# WT8266_universal_v01.net
KiCad netlist of a schematic drawn in EAGLE
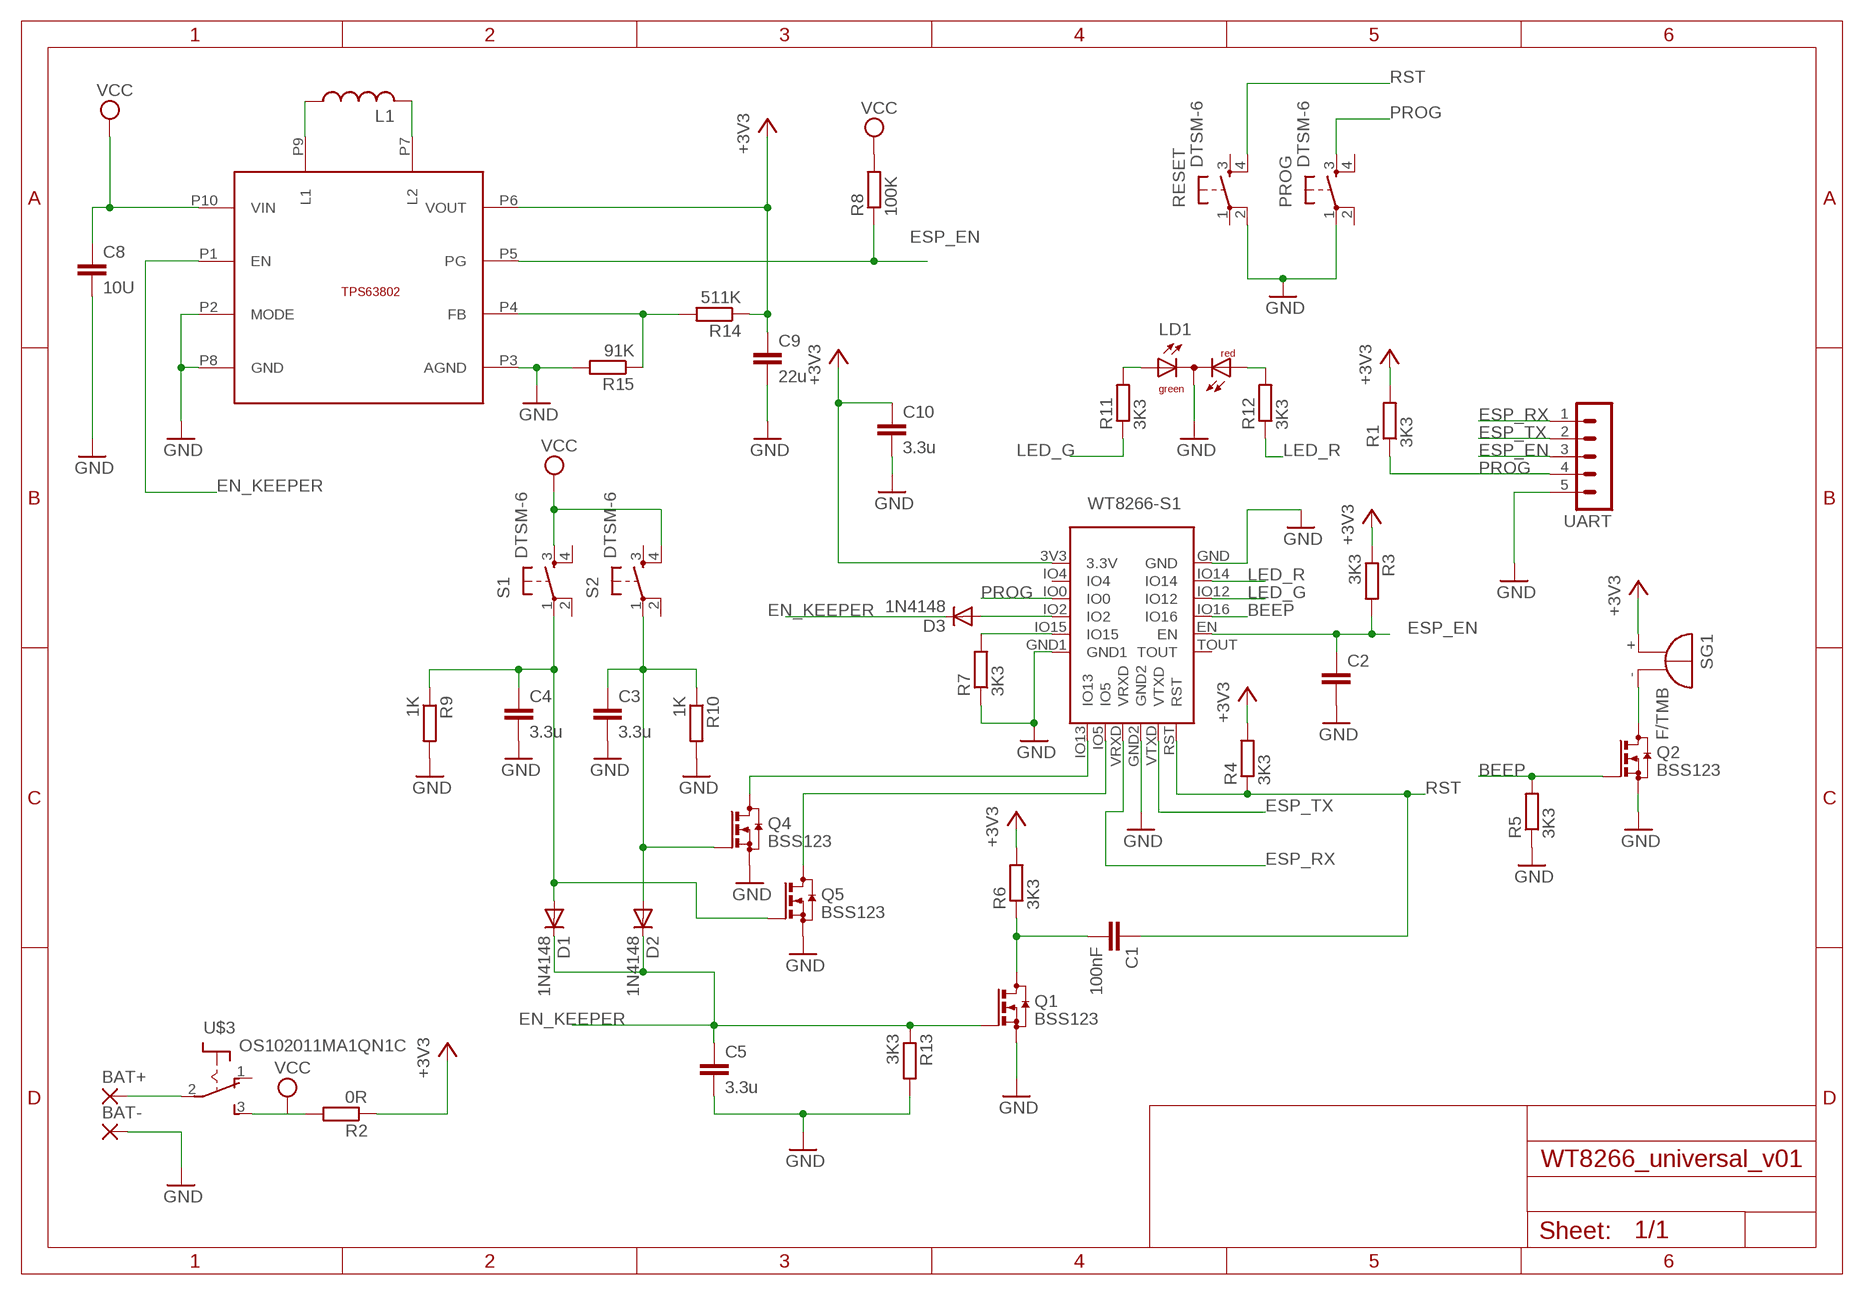
[diagram p0: schematic, sheet 1]

(export (version "E")
  (design (tool "Eeschema 10.0.6"))
  (components
    (comp (ref "BAT+")
      (value "2,54/1,0")
      (footprint "eagle-import:2,54_1,0")
      (libsource (lib "eagle-import") (part "2,54/1,0"))
    )
    (comp (ref "BAT-")
      (value "2,54/1,0")
      (footprint "eagle-import:2,54_1,0")
      (libsource (lib "eagle-import") (part "2,54/1,0"))
    )
    (comp (ref "C1")
      (value "100nF")
      (footprint "eagle-import:C0805")
      (libsource (lib "eagle-import") (part "C-EUC0805"))
    )
    (comp (ref "C2")
      (value "C-EUC0805")
      (footprint "eagle-import:C0805")
      (libsource (lib "eagle-import") (part "C-EUC0805"))
    )
    (comp (ref "C3")
      (value "3.3u")
      (footprint "eagle-import:C0805")
      (libsource (lib "eagle-import") (part "C-EUC0805"))
    )
    (comp (ref "C4")
      (value "3.3u")
      (footprint "eagle-import:C0805")
      (libsource (lib "eagle-import") (part "C-EUC0805"))
    )
    (comp (ref "C5")
      (value "3.3u")
      (footprint "eagle-import:C0805")
      (libsource (lib "eagle-import") (part "C-EUC0805"))
    )
    (comp (ref "C8")
      (value "10U")
      (footprint "eagle-import:C0805")
      (libsource (lib "eagle-import") (part "C-EUC0805"))
    )
    (comp (ref "C9")
      (value "22u")
      (footprint "eagle-import:C0805")
      (libsource (lib "eagle-import") (part "C-EUC0805"))
    )
    (comp (ref "C10")
      (value "3.3u")
      (footprint "eagle-import:C0805")
      (libsource (lib "eagle-import") (part "C-EUC0805"))
    )
    (comp (ref "D1")
      (value "1N4148")
      (footprint "eagle-import:0805")
      (libsource (lib "eagle-import") (part "1N4148"))
    )
    (comp (ref "D2")
      (value "1N4148")
      (footprint "eagle-import:0805")
      (libsource (lib "eagle-import") (part "1N4148"))
    )
    (comp (ref "D3")
      (value "1N4148")
      (footprint "eagle-import:0805")
      (libsource (lib "eagle-import") (part "1N4148"))
    )
    (comp (ref "L1")
      (value "L-USL2825P")
      (footprint "eagle-import:L2825P")
      (libsource (lib "eagle-import") (part "L-USL2825P"))
    )
    (comp (ref "LD1")
      (value "DUOLED-RG-C3MM")
      (footprint "eagle-import:DUOLED-A-3MM")
      (libsource (lib "eagle-import") (part "DUOLED-RG-C3MM"))
    )
    (comp (ref "PROG")
      (value "DTSM-6")
      (footprint "eagle-import:DTSM-6")
      (libsource (lib "eagle-import") (part "DTSM-6"))
    )
    (comp (ref "Q1")
      (value "BSS123")
      (footprint "eagle-import:SOT23")
      (libsource (lib "eagle-import") (part "BSS123"))
    )
    (comp (ref "Q2")
      (value "BSS123")
      (footprint "eagle-import:SOT23")
      (libsource (lib "eagle-import") (part "BSS123"))
    )
    (comp (ref "Q4")
      (value "BSS123")
      (footprint "eagle-import:SOT23")
      (libsource (lib "eagle-import") (part "BSS123"))
    )
    (comp (ref "Q5")
      (value "BSS123")
      (footprint "eagle-import:SOT23")
      (libsource (lib "eagle-import") (part "BSS123"))
    )
    (comp (ref "R1")
      (value "3K3")
      (footprint "eagle-import:R0805")
      (libsource (lib "eagle-import") (part "R-EU_R0805"))
    )
    (comp (ref "R2")
      (value "0R")
      (footprint "eagle-import:R0805")
      (libsource (lib "eagle-import") (part "R-EU_R0805"))
    )
    (comp (ref "R3")
      (value "3K3")
      (footprint "eagle-import:R0805")
      (libsource (lib "eagle-import") (part "R-EU_R0805"))
    )
    (comp (ref "R4")
      (value "3K3")
      (footprint "eagle-import:R0805")
      (libsource (lib "eagle-import") (part "R-EU_R0805"))
    )
    (comp (ref "R5")
      (value "3K3")
      (footprint "eagle-import:R0805")
      (libsource (lib "eagle-import") (part "R-EU_R0805"))
    )
    (comp (ref "R6")
      (value "3K3")
      (footprint "eagle-import:R0805")
      (libsource (lib "eagle-import") (part "R-EU_R0805"))
    )
    (comp (ref "R7")
      (value "3K3")
      (footprint "eagle-import:R0805")
      (libsource (lib "eagle-import") (part "R-EU_R0805"))
    )
    (comp (ref "R8")
      (value "100K")
      (footprint "eagle-import:R0805")
      (libsource (lib "eagle-import") (part "R-EU_R0805"))
    )
    (comp (ref "R9")
      (value "1K")
      (footprint "eagle-import:R0805")
      (libsource (lib "eagle-import") (part "R-EU_R0805"))
    )
    (comp (ref "R10")
      (value "1K")
      (footprint "eagle-import:R0805")
      (libsource (lib "eagle-import") (part "R-EU_R0805"))
    )
    (comp (ref "R11")
      (value "3K3")
      (footprint "eagle-import:R0805")
      (libsource (lib "eagle-import") (part "R-EU_R0805"))
    )
    (comp (ref "R12")
      (value "3K3")
      (footprint "eagle-import:R0805")
      (libsource (lib "eagle-import") (part "R-EU_R0805"))
    )
    (comp (ref "R13")
      (value "3K3")
      (footprint "eagle-import:R0805")
      (libsource (lib "eagle-import") (part "R-EU_R0805"))
    )
    (comp (ref "R14")
      (value "511K")
      (footprint "eagle-import:R0805")
      (libsource (lib "eagle-import") (part "R-EU_R0805"))
    )
    (comp (ref "R15")
      (value "91K")
      (footprint "eagle-import:R0805")
      (libsource (lib "eagle-import") (part "R-EU_R0805"))
    )
    (comp (ref "RESET")
      (value "DTSM-6")
      (footprint "eagle-import:DTSM-6")
      (libsource (lib "eagle-import") (part "DTSM-6"))
    )
    (comp (ref "S1")
      (value "DTSM-6")
      (footprint "eagle-import:DTSM-6")
      (libsource (lib "eagle-import") (part "DTSM-6"))
    )
    (comp (ref "S2")
      (value "DTSM-6")
      (footprint "eagle-import:DTSM-6")
      (libsource (lib "eagle-import") (part "DTSM-6"))
    )
    (comp (ref "SG1")
      (value "F/TMB")
      (footprint "eagle-import:F_TMB")
      (libsource (lib "eagle-import") (part "F/TMB"))
    )
    (comp (ref "U$1")
      (value "WT8266-S1")
      (footprint "eagle-import:WT8266-S1")
      (libsource (lib "eagle-import") (part "WT8266-S1"))
    )
    (comp (ref "U$3")
      (value "OS102011MA1QN1C")
      (footprint "eagle-import:OS102011MA1QN1C")
      (libsource (lib "eagle-import") (part "OS102011MA1QN1C"))
    )
    (comp (ref "U$4")
      (value "TPS63802")
      (footprint "eagle-import:VSON-HR-10")
      (libsource (lib "eagle-import") (part "TPS63802"))
    )
    (comp (ref "UART")
      (value "MAR05-1")
      (footprint "eagle-import:MAR05-1")
      (libsource (lib "eagle-import") (part "MAR05-1"))
    )
  )
  (nets
    (net (code "1") (name "+3V3") (class "Default")
      (node (ref "C10") (pin "1") (pinfunction "1_1") (pintype "passive"))
      (node (ref "C9") (pin "1") (pinfunction "1_1") (pintype "passive"))
      (node (ref "R1") (pin "2") (pinfunction "2_2") (pintype "passive"))
      (node (ref "R14") (pin "1") (pinfunction "1_1") (pintype "passive"))
      (node (ref "R2") (pin "1") (pinfunction "1_1") (pintype "passive"))
      (node (ref "R3") (pin "1") (pinfunction "1_1") (pintype "passive"))
      (node (ref "R4") (pin "2") (pinfunction "2_2") (pintype "passive"))
      (node (ref "R6") (pin "2") (pinfunction "2_2") (pintype "passive"))
      (node (ref "SG1") (pin "+") (pinfunction "+_+") (pintype "passive"))
      (node (ref "U$1") (pin "3V3") (pinfunction "3.3V_3V3") (pintype "bidirectional"))
      (node (ref "U$4") (pin "P6") (pinfunction "VOUT_P6") (pintype "bidirectional"))
    )
    (net (code "2") (name "/BEEP") (class "Default")
      (node (ref "Q2") (pin "1") (pinfunction "G_1") (pintype "passive"))
      (node (ref "R5") (pin "2") (pinfunction "2_2") (pintype "passive"))
      (node (ref "U$1") (pin "IO16") (pinfunction "IO16_IO16") (pintype "bidirectional"))
    )
    (net (code "3") (name "/EN_KEEPER") (class "Default")
      (node (ref "C5") (pin "1") (pinfunction "1_1") (pintype "passive"))
      (node (ref "D1") (pin "1") (pinfunction "C_1") (pintype "passive"))
      (node (ref "D2") (pin "1") (pinfunction "C_1") (pintype "passive"))
      (node (ref "D3") (pin "1") (pinfunction "C_1") (pintype "passive"))
      (node (ref "Q1") (pin "1") (pinfunction "G_1") (pintype "passive"))
      (node (ref "R13") (pin "1") (pinfunction "1_1") (pintype "passive"))
      (node (ref "U$4") (pin "P1") (pinfunction "EN_P1") (pintype "bidirectional"))
    )
    (net (code "4") (name "/ESP_EN") (class "Default")
      (node (ref "C2") (pin "1") (pinfunction "1_1") (pintype "passive"))
      (node (ref "R3") (pin "2") (pinfunction "2_2") (pintype "passive"))
      (node (ref "R8") (pin "1") (pinfunction "1_1") (pintype "passive"))
      (node (ref "U$1") (pin "EN") (pinfunction "EN_EN") (pintype "bidirectional"))
      (node (ref "U$4") (pin "P5") (pinfunction "PG_P5") (pintype "bidirectional"))
      (node (ref "UART") (pin "3") (pinfunction "3_3") (pintype "passive"))
    )
    (net (code "5") (name "/ESP_RX") (class "Default")
      (node (ref "U$1") (pin "VRXD") (pinfunction "VRXD_VRXD") (pintype "bidirectional"))
      (node (ref "UART") (pin "1") (pinfunction "1_1") (pintype "passive"))
    )
    (net (code "6") (name "/ESP_TX") (class "Default")
      (node (ref "U$1") (pin "VTXD") (pinfunction "VTXD_VTXD") (pintype "bidirectional"))
      (node (ref "UART") (pin "2") (pinfunction "2_2") (pintype "passive"))
    )
    (net (code "7") (name "/LED_G") (class "Default")
      (node (ref "R11") (pin "1") (pinfunction "1_1") (pintype "passive"))
      (node (ref "U$1") (pin "IO12") (pinfunction "IO12_IO12") (pintype "bidirectional"))
    )
    (net (code "8") (name "/LED_R") (class "Default")
      (node (ref "R12") (pin "1") (pinfunction "1_1") (pintype "passive"))
      (node (ref "U$1") (pin "IO14") (pinfunction "IO14_IO14") (pintype "bidirectional"))
    )
    (net (code "9") (name "/PROG") (class "Default")
      (node (ref "PROG") (pin "3") (pinfunction "3_3") (pintype "passive"))
      (node (ref "R1") (pin "1") (pinfunction "1_1") (pintype "passive"))
      (node (ref "U$1") (pin "IO0") (pinfunction "IO0_IO0") (pintype "bidirectional"))
      (node (ref "UART") (pin "4") (pinfunction "4_4") (pintype "passive"))
    )
    (net (code "10") (name "/RST") (class "Default")
      (node (ref "C1") (pin "1") (pinfunction "1_1") (pintype "passive"))
      (node (ref "R4") (pin "1") (pinfunction "1_1") (pintype "passive"))
      (node (ref "RESET") (pin "4") (pinfunction "4_4") (pintype "passive"))
      (node (ref "U$1") (pin "RST") (pinfunction "RST_RST") (pintype "bidirectional"))
    )
    (net (code "11") (name "GND") (class "Default")
      (node (ref "BAT-") (pin "1") (pinfunction "P_1") (pintype "passive"))
      (node (ref "C10") (pin "2") (pinfunction "2_2") (pintype "passive"))
      (node (ref "C2") (pin "2") (pinfunction "2_2") (pintype "passive"))
      (node (ref "C3") (pin "2") (pinfunction "2_2") (pintype "passive"))
      (node (ref "C4") (pin "2") (pinfunction "2_2") (pintype "passive"))
      (node (ref "C5") (pin "2") (pinfunction "2_2") (pintype "passive"))
      (node (ref "C8") (pin "2") (pinfunction "2_2") (pintype "passive"))
      (node (ref "C9") (pin "2") (pinfunction "2_2") (pintype "passive"))
      (node (ref "LD1") (pin "2") (pinfunction "C_2") (pintype "passive"))
      (node (ref "PROG") (pin "1") (pinfunction "1_1") (pintype "passive"))
      (node (ref "Q1") (pin "2") (pinfunction "S_2") (pintype "passive"))
      (node (ref "Q2") (pin "2") (pinfunction "S_2") (pintype "passive"))
      (node (ref "Q4") (pin "2") (pinfunction "S_2") (pintype "passive"))
      (node (ref "Q5") (pin "2") (pinfunction "S_2") (pintype "passive"))
      (node (ref "R10") (pin "2") (pinfunction "2_2") (pintype "passive"))
      (node (ref "R13") (pin "2") (pinfunction "2_2") (pintype "passive"))
      (node (ref "R15") (pin "2") (pinfunction "2_2") (pintype "passive"))
      (node (ref "R5") (pin "1") (pinfunction "1_1") (pintype "passive"))
      (node (ref "R7") (pin "1") (pinfunction "1_1") (pintype "passive"))
      (node (ref "R9") (pin "2") (pinfunction "2_2") (pintype "passive"))
      (node (ref "RESET") (pin "2") (pinfunction "2_2") (pintype "passive"))
      (node (ref "U$1") (pin "GND") (pinfunction "GND_GND") (pintype "bidirectional"))
      (node (ref "U$1") (pin "GND1") (pinfunction "GND1_GND1") (pintype "bidirectional"))
      (node (ref "U$1") (pin "GND2") (pinfunction "GND2_GND2") (pintype "bidirectional"))
      (node (ref "U$4") (pin "P2") (pinfunction "MODE_P2") (pintype "bidirectional"))
      (node (ref "U$4") (pin "P3") (pinfunction "AGND_P3") (pintype "bidirectional"))
      (node (ref "U$4") (pin "P8") (pinfunction "GND_P8") (pintype "bidirectional"))
      (node (ref "UART") (pin "5") (pinfunction "5_5") (pintype "passive"))
    )
    (net (code "12") (name "Net-(BAT+-P)") (class "Default")
      (node (ref "BAT+") (pin "1") (pinfunction "P_1") (pintype "passive"))
      (node (ref "U$3") (pin "2") (pinfunction "P_2") (pintype "passive"))
    )
    (net (code "13") (name "Net-(D1-A)") (class "Default")
      (node (ref "C4") (pin "1") (pinfunction "1_1") (pintype "passive"))
      (node (ref "D1") (pin "2") (pinfunction "A_2") (pintype "passive"))
      (node (ref "Q5") (pin "1") (pinfunction "G_1") (pintype "passive"))
      (node (ref "R9") (pin "1") (pinfunction "1_1") (pintype "passive"))
      (node (ref "S1") (pin "1") (pinfunction "1_1") (pintype "passive"))
    )
    (net (code "14") (name "Net-(D2-A)") (class "Default")
      (node (ref "C3") (pin "1") (pinfunction "1_1") (pintype "passive"))
      (node (ref "D2") (pin "2") (pinfunction "A_2") (pintype "passive"))
      (node (ref "Q4") (pin "1") (pinfunction "G_1") (pintype "passive"))
      (node (ref "R10") (pin "1") (pinfunction "1_1") (pintype "passive"))
      (node (ref "S2") (pin "1") (pinfunction "1_1") (pintype "passive"))
    )
    (net (code "15") (name "Net-(D3-A)") (class "Default")
      (node (ref "D3") (pin "2") (pinfunction "A_2") (pintype "passive"))
      (node (ref "U$1") (pin "IO2") (pinfunction "IO2_IO2") (pintype "bidirectional"))
    )
    (net (code "16") (name "Net-(LD1-AG)") (class "Default")
      (node (ref "LD1") (pin "1") (pinfunction "AG_1") (pintype "passive"))
      (node (ref "R11") (pin "2") (pinfunction "2_2") (pintype "passive"))
    )
    (net (code "17") (name "Net-(LD1-AR)") (class "Default")
      (node (ref "LD1") (pin "3") (pinfunction "AR_3") (pintype "passive"))
      (node (ref "R12") (pin "2") (pinfunction "2_2") (pintype "passive"))
    )
    (net (code "18") (name "Net-(Q1-D)") (class "Default")
      (node (ref "C1") (pin "2") (pinfunction "2_2") (pintype "passive"))
      (node (ref "Q1") (pin "3") (pinfunction "D_3") (pintype "passive"))
      (node (ref "R6") (pin "1") (pinfunction "1_1") (pintype "passive"))
    )
    (net (code "19") (name "Net-(Q2-D)") (class "Default")
      (node (ref "Q2") (pin "3") (pinfunction "D_3") (pintype "passive"))
      (node (ref "SG1") (pin "-") (pinfunction "-_-") (pintype "passive"))
    )
    (net (code "20") (name "Net-(Q4-D)") (class "Default")
      (node (ref "Q4") (pin "3") (pinfunction "D_3") (pintype "passive"))
      (node (ref "U$1") (pin "IO13") (pinfunction "IO13_IO13") (pintype "bidirectional"))
    )
    (net (code "21") (name "Net-(Q5-D)") (class "Default")
      (node (ref "Q5") (pin "3") (pinfunction "D_3") (pintype "passive"))
      (node (ref "U$1") (pin "IO5") (pinfunction "IO5_IO5") (pintype "bidirectional"))
    )
    (net (code "22") (name "Net-(R7-Pad2)") (class "Default")
      (node (ref "R7") (pin "2") (pinfunction "2_2") (pintype "passive"))
      (node (ref "U$1") (pin "IO15") (pinfunction "IO15_IO15") (pintype "bidirectional"))
    )
    (net (code "23") (name "Net-(U$4-FB)") (class "Default")
      (node (ref "R14") (pin "2") (pinfunction "2_2") (pintype "passive"))
      (node (ref "R15") (pin "1") (pinfunction "1_1") (pintype "passive"))
      (node (ref "U$4") (pin "P4") (pinfunction "FB_P4") (pintype "bidirectional"))
    )
    (net (code "24") (name "Net-(U$4-L1)") (class "Default")
      (node (ref "L1") (pin "1") (pinfunction "1_1") (pintype "passive"))
      (node (ref "U$4") (pin "P9") (pinfunction "L1_P9") (pintype "bidirectional"))
    )
    (net (code "25") (name "Net-(U$4-L2)") (class "Default")
      (node (ref "L1") (pin "2") (pinfunction "2_2") (pintype "passive"))
      (node (ref "U$4") (pin "P7") (pinfunction "L2_P7") (pintype "bidirectional"))
    )
    (net (code "26") (name "VCC") (class "Default")
      (node (ref "C8") (pin "1") (pinfunction "1_1") (pintype "passive"))
      (node (ref "R2") (pin "2") (pinfunction "2_2") (pintype "passive"))
      (node (ref "R8") (pin "2") (pinfunction "2_2") (pintype "passive"))
      (node (ref "S1") (pin "3") (pinfunction "3_3") (pintype "passive"))
      (node (ref "S2") (pin "4") (pinfunction "4_4") (pintype "passive"))
      (node (ref "U$3") (pin "3") (pinfunction "S_3") (pintype "passive"))
      (node (ref "U$4") (pin "P10") (pinfunction "VIN_P10") (pintype "bidirectional"))
    )
    (net (code "27") (name "unconnected-(PROG-Pad2)") (class "Default")
      (node (ref "PROG") (pin "2") (pinfunction "2_2") (pintype "passive"))
    )
    (net (code "28") (name "unconnected-(PROG-Pad4)") (class "Default")
      (node (ref "PROG") (pin "4") (pinfunction "4_4") (pintype "passive"))
    )
    (net (code "29") (name "unconnected-(RESET-Pad1)") (class "Default")
      (node (ref "RESET") (pin "1") (pinfunction "1_1") (pintype "passive"))
    )
    (net (code "30") (name "unconnected-(RESET-Pad3)") (class "Default")
      (node (ref "RESET") (pin "3") (pinfunction "3_3") (pintype "passive"))
    )
    (net (code "31") (name "unconnected-(S1-Pad2)") (class "Default")
      (node (ref "S1") (pin "2") (pinfunction "2_2") (pintype "passive"))
    )
    (net (code "32") (name "unconnected-(S1-Pad4)") (class "Default")
      (node (ref "S1") (pin "4") (pinfunction "4_4") (pintype "passive"))
    )
    (net (code "33") (name "unconnected-(S2-Pad2)") (class "Default")
      (node (ref "S2") (pin "2") (pinfunction "2_2") (pintype "passive"))
    )
    (net (code "34") (name "unconnected-(S2-Pad3)") (class "Default")
      (node (ref "S2") (pin "3") (pinfunction "3_3") (pintype "passive"))
    )
    (net (code "35") (name "unconnected-(U$1-PadIO4)") (class "Default")
      (node (ref "U$1") (pin "IO4") (pinfunction "IO4_IO4") (pintype "bidirectional"))
    )
    (net (code "36") (name "unconnected-(U$1-PadTOUT)") (class "Default")
      (node (ref "U$1") (pin "TOUT") (pinfunction "TOUT_TOUT") (pintype "bidirectional"))
    )
    (net (code "37") (name "unconnected-(U$3-O-Pad1)") (class "Default")
      (node (ref "U$3") (pin "1") (pinfunction "O_1") (pintype "passive"))
    )
  )
)
